# dosimeter.net
KiCad netlist of a schematic drawn in EAGLE
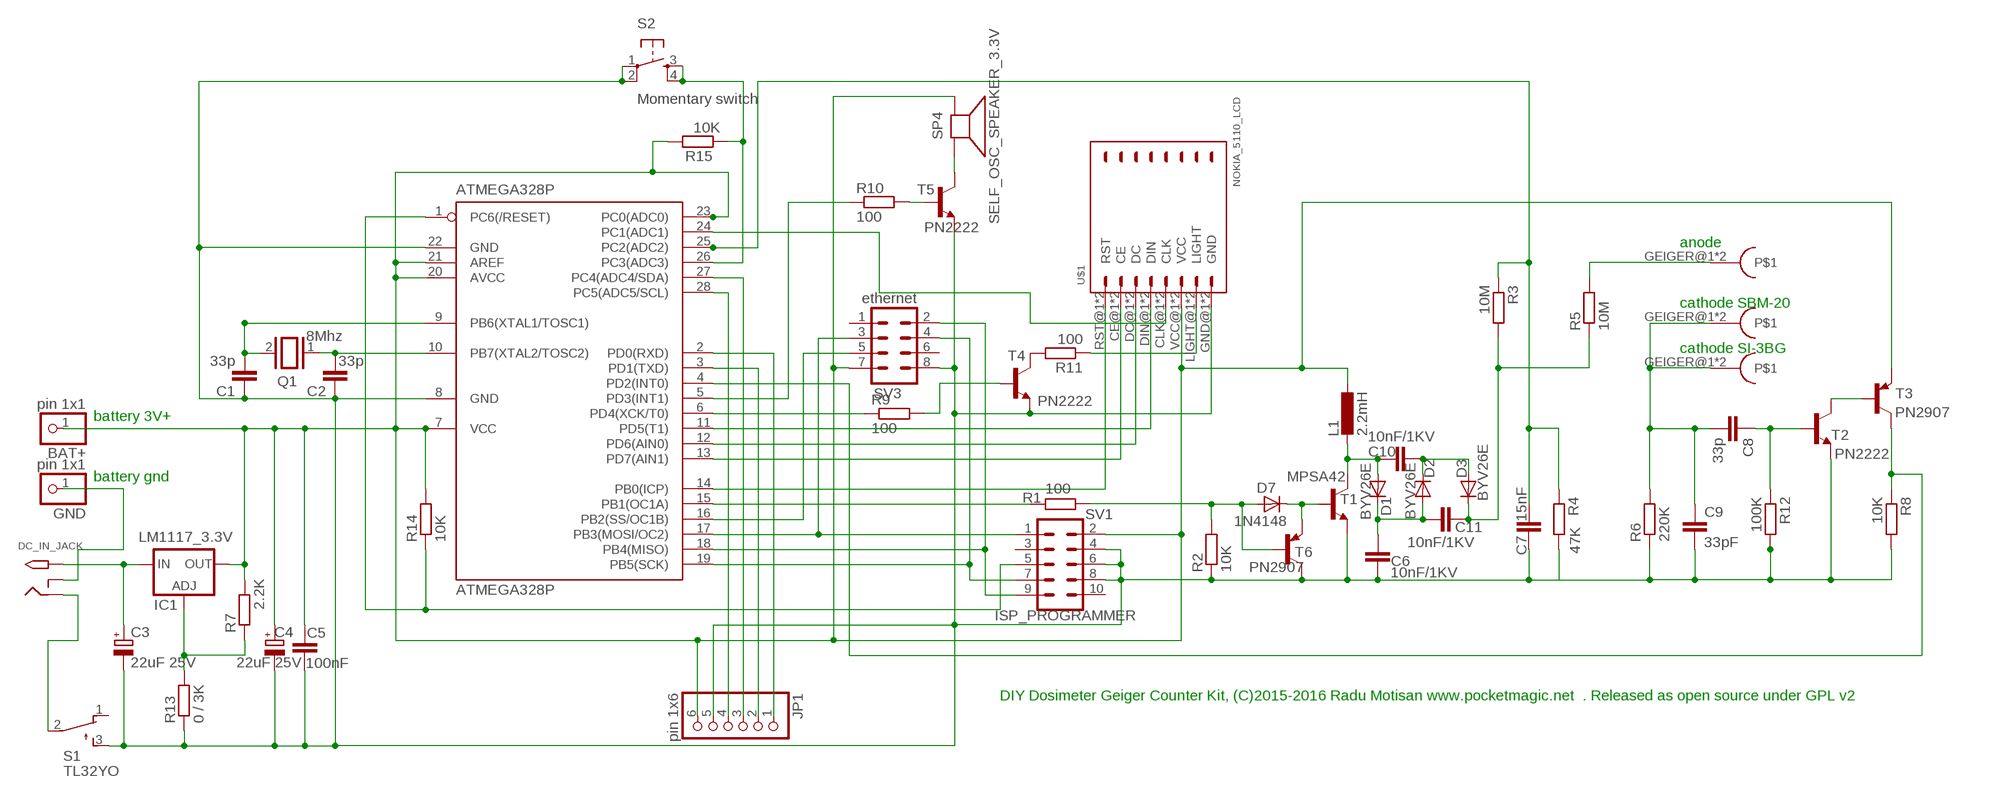
[diagram p0: schematic, sheet 1]

(export (version "E")
  (design (tool "Eeschema 10.0.6"))
  (components
    (comp (ref "ATMEGA328P")
      (value "ATMEGA328P")
      (footprint "eagle-import:DIL28-3")
      (libsource (lib "eagle-import") (part "MEGA8-P"))
    )
    (comp (ref "BAT+")
      (value "pin 1x1")
      (footprint "eagle-import:1X01")
      (libsource (lib "eagle-import") (part "PINHD-1X1"))
    )
    (comp (ref "C1")
      (value "33p")
      (footprint "eagle-import:C2.5-2")
      (libsource (lib "eagle-import") (part "C2.5/2"))
    )
    (comp (ref "C2")
      (value "33p")
      (footprint "eagle-import:C2.5-2")
      (libsource (lib "eagle-import") (part "C2.5/2"))
    )
    (comp (ref "C3")
      (value "22uF 25V")
      (footprint "eagle-import:E2-5")
      (libsource (lib "eagle-import") (part "CPOL-EUE2-5"))
    )
    (comp (ref "C4")
      (value "22uF 25V")
      (footprint "eagle-import:E2-5")
      (libsource (lib "eagle-import") (part "CPOL-EUE2-5"))
    )
    (comp (ref "C5")
      (value "100nF")
      (footprint "eagle-import:C2.5-2")
      (libsource (lib "eagle-import") (part "C2.5/2"))
    )
    (comp (ref "C6")
      (value "10nF/1KV")
      (footprint "eagle-import:C5B3")
      (libsource (lib "eagle-import") (part "C5/3"))
    )
    (comp (ref "C7")
      (value "15nF")
      (footprint "eagle-import:C2.5-2")
      (libsource (lib "eagle-import") (part "C2.5/2"))
    )
    (comp (ref "C8")
      (value "33p")
      (footprint "eagle-import:C2.5-2")
      (libsource (lib "eagle-import") (part "C2.5/2"))
    )
    (comp (ref "C9")
      (value "33pF")
      (footprint "eagle-import:C2.5-2")
      (libsource (lib "eagle-import") (part "C2.5/2"))
    )
    (comp (ref "C10")
      (value "10nF/1KV")
      (footprint "eagle-import:C5B3")
      (libsource (lib "eagle-import") (part "C5/3"))
    )
    (comp (ref "C11")
      (value "10nF/1KV")
      (footprint "eagle-import:C5B3")
      (libsource (lib "eagle-import") (part "C5/3"))
    )
    (comp (ref "CONNECTOR1")
      (value "Fuse connector 6mm")
      (footprint "eagle-import:GEIGER_CONNECTOR")
      (libsource (lib "eagle-import") (part "GEIGER_CONNECTOR"))
    )
    (comp (ref "CONNECTOR2")
      (value "Fuse connector 6mm")
      (footprint "eagle-import:GEIGER_CONNECTOR")
      (libsource (lib "eagle-import") (part "GEIGER_CONNECTOR"))
    )
    (comp (ref "CONNECTOR3")
      (value "Fuse connector 6mm")
      (footprint "eagle-import:GEIGER_CONNECTOR")
      (libsource (lib "eagle-import") (part "GEIGER_CONNECTOR"))
    )
    (comp (ref "D1")
      (value "BYV26E")
      (footprint "eagle-import:D-7.5")
      (libsource (lib "eagle-import") (part "1N40047.5"))
    )
    (comp (ref "D2")
      (value "BYV26E")
      (footprint "eagle-import:D-7.5")
      (libsource (lib "eagle-import") (part "1N40047.5"))
    )
    (comp (ref "D3")
      (value "BYV26E")
      (footprint "eagle-import:D-7.5")
      (libsource (lib "eagle-import") (part "1N40047.5"))
    )
    (comp (ref "D7")
      (value "1N4148")
      (footprint "eagle-import:DO35-7")
      (libsource (lib "eagle-import") (part "1N4148DO35-7"))
    )
    (comp (ref "DC_IN_JACK")
      (value "DC IN JACK")
      (footprint "eagle-import:PJ-102A")
      (libsource (lib "eagle-import") (part "2.1MMJACKTHM"))
    )
    (comp (ref "GND")
      (value "pin 1x1")
      (footprint "eagle-import:1X01")
      (libsource (lib "eagle-import") (part "PINHD-1X1"))
    )
    (comp (ref "IC1")
      (value "LM1117_3.3V")
      (footprint "eagle-import:TO220L1")
      (libsource (lib "eagle-import") (part "LD117A?V"))
    )
    (comp (ref "JP1")
      (value "pin 1x6")
      (footprint "eagle-import:1X06-CLEAN")
      (libsource (lib "eagle-import") (part "PINHD-1X6CLEAN"))
    )
    (comp (ref "L1")
      (value "2.2mH")
      (footprint "eagle-import:0207_10")
      (libsource (lib "eagle-import") (part "L-EU0207/10"))
    )
    (comp (ref "Q1")
      (value "8Mhz")
      (footprint "eagle-import:QS")
      (libsource (lib "eagle-import") (part "XTAL/S"))
    )
    (comp (ref "R1")
      (value "100")
      (footprint "eagle-import:0204_7")
      (libsource (lib "eagle-import") (part "R-EU_0204/7"))
    )
    (comp (ref "R2")
      (value "10K")
      (footprint "eagle-import:0204_7")
      (libsource (lib "eagle-import") (part "R-EU_0204/7"))
    )
    (comp (ref "R3")
      (value "10M")
      (footprint "eagle-import:0204_7")
      (libsource (lib "eagle-import") (part "R-EU_0204/7"))
    )
    (comp (ref "R4")
      (value "47K")
      (footprint "eagle-import:0204_7")
      (libsource (lib "eagle-import") (part "R-EU_0204/7"))
    )
    (comp (ref "R5")
      (value "10M")
      (footprint "eagle-import:0204_7")
      (libsource (lib "eagle-import") (part "R-EU_0204/7"))
    )
    (comp (ref "R6")
      (value "220K")
      (footprint "eagle-import:0204_7")
      (libsource (lib "eagle-import") (part "R-EU_0204/7"))
    )
    (comp (ref "R7")
      (value "2.2K")
      (footprint "eagle-import:0204_7")
      (libsource (lib "eagle-import") (part "R-EU_0204/7"))
    )
    (comp (ref "R8")
      (value "10K")
      (footprint "eagle-import:0204_7")
      (libsource (lib "eagle-import") (part "R-EU_0204/7"))
    )
    (comp (ref "R9")
      (value "100")
      (footprint "eagle-import:0204_7")
      (libsource (lib "eagle-import") (part "R-EU_0204/7"))
    )
    (comp (ref "R10")
      (value "100")
      (footprint "eagle-import:0204_7")
      (libsource (lib "eagle-import") (part "R-EU_0204/7"))
    )
    (comp (ref "R11")
      (value "100")
      (footprint "eagle-import:0204_7")
      (libsource (lib "eagle-import") (part "R-EU_0204/7"))
    )
    (comp (ref "R12")
      (value "100K")
      (footprint "eagle-import:0204_7")
      (libsource (lib "eagle-import") (part "R-EU_0204/7"))
    )
    (comp (ref "R13")
      (value "0 / 3K")
      (footprint "eagle-import:0204_7")
      (libsource (lib "eagle-import") (part "R-EU_0204/7"))
    )
    (comp (ref "R14")
      (value "10K")
      (footprint "eagle-import:0204_7")
      (libsource (lib "eagle-import") (part "R-EU_0204/7"))
    )
    (comp (ref "R15")
      (value "10K")
      (footprint "eagle-import:0204_7")
      (libsource (lib "eagle-import") (part "R-EU_0204/7"))
    )
    (comp (ref "S1")
      (value "TL32YO")
      (footprint "eagle-import:TL3XYO")
      (libsource (lib "eagle-import") (part "TL32YO"))
    )
    (comp (ref "S2")
      (value "Momentary switch")
      (footprint "eagle-import:TACTILE-PTH")
      (libsource (lib "eagle-import") (part "TAC_SWITCHPTH"))
    )
    (comp (ref "SP4")
      (value "SELF_OSC_SPEAKER_3.3V")
      (footprint "eagle-import:AL60P")
      (libsource (lib "eagle-import") (part "SPEAKER/AL60P"))
    )
    (comp (ref "SV1")
      (value "ISP_PROGRAMMER")
      (footprint "eagle-import:MA05-2")
      (libsource (lib "eagle-import") (part "MA05-2"))
    )
    (comp (ref "SV3")
      (value "ethernet")
      (footprint "eagle-import:MA04-2")
      (libsource (lib "eagle-import") (part "MA04-2"))
    )
    (comp (ref "T1")
      (value "MPSA42")
      (footprint "eagle-import:TO92-EBC-OVAL")
      (libsource (lib "eagle-import") (part "2N2222"))
    )
    (comp (ref "T2")
      (value "PN2222")
      (footprint "eagle-import:TO92-EBC-OVAL")
      (libsource (lib "eagle-import") (part "2N2222"))
    )
    (comp (ref "T3")
      (value "PN2907")
      (footprint "eagle-import:TO92-EBC-OVAL")
      (libsource (lib "eagle-import") (part "2N2907"))
    )
    (comp (ref "T4")
      (value "PN2222")
      (footprint "eagle-import:TO92-EBC")
      (libsource (lib "eagle-import") (part "-NPN-TO92-EBC2N2222"))
    )
    (comp (ref "T5")
      (value "PN2222")
      (footprint "eagle-import:TO92-EBC")
      (libsource (lib "eagle-import") (part "-NPN-TO92-EBC2N2222"))
    )
    (comp (ref "T6")
      (value "PN2907")
      (footprint "eagle-import:TO92-EBC-OVAL")
      (libsource (lib "eagle-import") (part "2N2907"))
    )
    (comp (ref "U$1")
      (value "NOKIA_5110_LCD")
      (footprint "eagle-import:NOKIA5110")
      (libsource (lib "eagle-import") (part "NOKIA5110"))
    )
  )
  (nets
    (net (code "1") (name "Net-(ATMEGA328P-AREF)") (class "Default")
      (node (ref "ATMEGA328P") (pin "20") (pinfunction "AVCC_20") (pintype "power_in"))
      (node (ref "ATMEGA328P") (pin "21") (pinfunction "AREF_21") (pintype "passive"))
      (node (ref "ATMEGA328P") (pin "23") (pinfunction "PC0(ADC0)_23") (pintype "bidirectional"))
      (node (ref "ATMEGA328P") (pin "7") (pinfunction "VCC_7") (pintype "power_in"))
      (node (ref "BAT+") (pin "1") (pinfunction "1_1") (pintype "passive"))
      (node (ref "C4") (pin "+") (pinfunction "+_+") (pintype "passive"))
      (node (ref "C5") (pin "2") (pinfunction "2_2") (pintype "passive"))
      (node (ref "IC1") (pin "2") (pinfunction "OUT_2") (pintype "passive"))
      (node (ref "JP1") (pin "6") (pinfunction "6_6") (pintype "passive"))
      (node (ref "L1") (pin "1") (pinfunction "1_1") (pintype "passive"))
      (node (ref "R14") (pin "2") (pinfunction "2_2") (pintype "passive"))
      (node (ref "R15") (pin "2") (pinfunction "2_2") (pintype "passive"))
      (node (ref "R7") (pin "2") (pinfunction "2_2") (pintype "passive"))
      (node (ref "SP4") (pin "1") (pinfunction "+_1") (pintype "passive"))
      (node (ref "SV1") (pin "2") (pinfunction "2_2") (pintype "passive"))
      (node (ref "SV3") (pin "7") (pinfunction "7_7") (pintype "passive"))
      (node (ref "T3") (pin "E") (pinfunction "E_E") (pintype "passive"))
      (node (ref "U$1") (pin "VCC@1") (pinfunction "VCC_VCC@1") (pintype "bidirectional"))
      (node (ref "U$1") (pin "VCC@2") (pinfunction "VCC_VCC@2") (pintype "bidirectional"))
    )
    (net (code "2") (name "Net-(ATMEGA328P-PB0(ICP))") (class "Default")
      (node (ref "ATMEGA328P") (pin "14") (pinfunction "PB0(ICP)_14") (pintype "bidirectional"))
      (node (ref "U$1") (pin "RST@1") (pinfunction "RST_RST@1") (pintype "bidirectional"))
      (node (ref "U$1") (pin "RST@2") (pinfunction "RST_RST@2") (pintype "bidirectional"))
    )
    (net (code "3") (name "Net-(ATMEGA328P-PB1(OC1A))") (class "Default")
      (node (ref "ATMEGA328P") (pin "15") (pinfunction "PB1(OC1A)_15") (pintype "bidirectional"))
      (node (ref "R1") (pin "1") (pinfunction "1_1") (pintype "passive"))
    )
    (net (code "4") (name "Net-(ATMEGA328P-PB2(SS{slash}OC1B))") (class "Default")
      (node (ref "ATMEGA328P") (pin "16") (pinfunction "PB2(SS/OC1B)_16") (pintype "bidirectional"))
      (node (ref "SV3") (pin "5") (pinfunction "5_5") (pintype "passive"))
    )
    (net (code "5") (name "Net-(ATMEGA328P-PB3(MOSI{slash}OC2))") (class "Default")
      (node (ref "ATMEGA328P") (pin "17") (pinfunction "PB3(MOSI/OC2)_17") (pintype "bidirectional"))
      (node (ref "SV1") (pin "1") (pinfunction "1_1") (pintype "passive"))
      (node (ref "SV3") (pin "3") (pinfunction "3_3") (pintype "passive"))
    )
    (net (code "6") (name "Net-(ATMEGA328P-PB4(MISO))") (class "Default")
      (node (ref "ATMEGA328P") (pin "18") (pinfunction "PB4(MISO)_18") (pintype "bidirectional"))
      (node (ref "SV1") (pin "9") (pinfunction "9_9") (pintype "passive"))
      (node (ref "SV3") (pin "2") (pinfunction "2_2") (pintype "passive"))
    )
    (net (code "7") (name "Net-(ATMEGA328P-PB5(SCK))") (class "Default")
      (node (ref "ATMEGA328P") (pin "19") (pinfunction "PB5(SCK)_19") (pintype "bidirectional"))
      (node (ref "SV1") (pin "7") (pinfunction "7_7") (pintype "passive"))
      (node (ref "SV3") (pin "4") (pinfunction "4_4") (pintype "passive"))
    )
    (net (code "8") (name "Net-(ATMEGA328P-PB6(XTAL1{slash}TOSC1))") (class "Default")
      (node (ref "ATMEGA328P") (pin "9") (pinfunction "PB6(XTAL1/TOSC1)_9") (pintype "bidirectional"))
      (node (ref "C1") (pin "2") (pinfunction "2_2") (pintype "passive"))
      (node (ref "Q1") (pin "2") (pinfunction "2_2") (pintype "passive"))
    )
    (net (code "9") (name "Net-(ATMEGA328P-PB7(XTAL2{slash}TOSC2))") (class "Default")
      (node (ref "ATMEGA328P") (pin "10") (pinfunction "PB7(XTAL2/TOSC2)_10") (pintype "bidirectional"))
      (node (ref "C2") (pin "2") (pinfunction "2_2") (pintype "passive"))
      (node (ref "Q1") (pin "1") (pinfunction "1_1") (pintype "passive"))
    )
    (net (code "10") (name "Net-(ATMEGA328P-PC1(ADC1))") (class "Default")
      (node (ref "ATMEGA328P") (pin "24") (pinfunction "PC1(ADC1)_24") (pintype "bidirectional"))
      (node (ref "U$1") (pin "CLK@1") (pinfunction "CLK_CLK@1") (pintype "bidirectional"))
      (node (ref "U$1") (pin "CLK@2") (pinfunction "CLK_CLK@2") (pintype "bidirectional"))
    )
    (net (code "11") (name "Net-(ATMEGA328P-PC2(ADC2))") (class "Default")
      (node (ref "ATMEGA328P") (pin "25") (pinfunction "PC2(ADC2)_25") (pintype "bidirectional"))
      (node (ref "C7") (pin "2") (pinfunction "2_2") (pintype "passive"))
      (node (ref "R3") (pin "1") (pinfunction "1_1") (pintype "passive"))
      (node (ref "R4") (pin "1") (pinfunction "1_1") (pintype "passive"))
    )
    (net (code "12") (name "Net-(ATMEGA328P-PC3(ADC3))") (class "Default")
      (node (ref "ATMEGA328P") (pin "26") (pinfunction "PC3(ADC3)_26") (pintype "bidirectional"))
      (node (ref "R15") (pin "1") (pinfunction "1_1") (pintype "passive"))
      (node (ref "S2") (pin "3") (pinfunction "3_3") (pintype "passive"))
      (node (ref "S2") (pin "4") (pinfunction "4_4") (pintype "passive"))
    )
    (net (code "13") (name "Net-(ATMEGA328P-PC4(ADC4{slash}SDA))") (class "Default")
      (node (ref "ATMEGA328P") (pin "27") (pinfunction "PC4(ADC4/SDA)_27") (pintype "bidirectional"))
      (node (ref "JP1") (pin "3") (pinfunction "3_3") (pintype "passive"))
    )
    (net (code "14") (name "Net-(ATMEGA328P-PC5(ADC5{slash}SCL))") (class "Default")
      (node (ref "ATMEGA328P") (pin "28") (pinfunction "PC5(ADC5/SCL)_28") (pintype "bidirectional"))
      (node (ref "JP1") (pin "4") (pinfunction "4_4") (pintype "passive"))
    )
    (net (code "15") (name "Net-(ATMEGA328P-PC6({slash}RESET))") (class "Default")
      (node (ref "ATMEGA328P") (pin "1") (pinfunction "PC6(/RESET)_1") (pintype "bidirectional"))
      (node (ref "R14") (pin "1") (pinfunction "1_1") (pintype "passive"))
      (node (ref "SV1") (pin "5") (pinfunction "5_5") (pintype "passive"))
    )
    (net (code "16") (name "Net-(ATMEGA328P-PD0(RXD))") (class "Default")
      (node (ref "ATMEGA328P") (pin "2") (pinfunction "PD0(RXD)_2") (pintype "bidirectional"))
      (node (ref "JP1") (pin "1") (pinfunction "1_1") (pintype "passive"))
    )
    (net (code "17") (name "Net-(ATMEGA328P-PD1(TXD))") (class "Default")
      (node (ref "ATMEGA328P") (pin "3") (pinfunction "PD1(TXD)_3") (pintype "bidirectional"))
      (node (ref "JP1") (pin "2") (pinfunction "2_2") (pintype "passive"))
    )
    (net (code "18") (name "Net-(ATMEGA328P-PD2(INT0))") (class "Default")
      (node (ref "ATMEGA328P") (pin "4") (pinfunction "PD2(INT0)_4") (pintype "bidirectional"))
      (node (ref "R8") (pin "1") (pinfunction "1_1") (pintype "passive"))
      (node (ref "T3") (pin "C") (pinfunction "C_C") (pintype "passive"))
    )
    (net (code "19") (name "Net-(ATMEGA328P-PD3(INT1))") (class "Default")
      (node (ref "ATMEGA328P") (pin "5") (pinfunction "PD3(INT1)_5") (pintype "bidirectional"))
      (node (ref "R10") (pin "1") (pinfunction "1_1") (pintype "passive"))
    )
    (net (code "20") (name "Net-(ATMEGA328P-PD4(XCK{slash}T0))") (class "Default")
      (node (ref "ATMEGA328P") (pin "6") (pinfunction "PD4(XCK/T0)_6") (pintype "bidirectional"))
      (node (ref "R9") (pin "1") (pinfunction "1_1") (pintype "passive"))
    )
    (net (code "21") (name "Net-(ATMEGA328P-PD5(T1))") (class "Default")
      (node (ref "ATMEGA328P") (pin "11") (pinfunction "PD5(T1)_11") (pintype "bidirectional"))
      (node (ref "U$1") (pin "DIN@1") (pinfunction "DIN_DIN@1") (pintype "bidirectional"))
      (node (ref "U$1") (pin "DIN@2") (pinfunction "DIN_DIN@2") (pintype "bidirectional"))
    )
    (net (code "22") (name "Net-(ATMEGA328P-PD6(AIN0))") (class "Default")
      (node (ref "ATMEGA328P") (pin "12") (pinfunction "PD6(AIN0)_12") (pintype "bidirectional"))
      (node (ref "U$1") (pin "DC@1") (pinfunction "DC_DC@1") (pintype "bidirectional"))
      (node (ref "U$1") (pin "DC@2") (pinfunction "DC_DC@2") (pintype "bidirectional"))
    )
    (net (code "23") (name "Net-(ATMEGA328P-PD7(AIN1))") (class "Default")
      (node (ref "ATMEGA328P") (pin "13") (pinfunction "PD7(AIN1)_13") (pintype "bidirectional"))
      (node (ref "U$1") (pin "CE@1") (pinfunction "CE_CE@1") (pintype "bidirectional"))
      (node (ref "U$1") (pin "CE@2") (pinfunction "CE_CE@2") (pintype "bidirectional"))
    )
    (net (code "24") (name "Net-(C8-Pad1)") (class "Default")
      (node (ref "C8") (pin "1") (pinfunction "1_1") (pintype "passive"))
      (node (ref "R12") (pin "1") (pinfunction "1_1") (pintype "passive"))
      (node (ref "T2") (pin "B") (pinfunction "B_B") (pintype "passive"))
    )
    (net (code "25") (name "Net-(C8-Pad2)") (class "Default")
      (node (ref "C8") (pin "2") (pinfunction "2_2") (pintype "passive"))
      (node (ref "C9") (pin "1") (pinfunction "1_1") (pintype "passive"))
      (node (ref "CONNECTOR1") (pin "GEIGER@1") (pinfunction "P$1_GEIGER@1") (pintype "bidirectional"))
      (node (ref "CONNECTOR1") (pin "GEIGER@2") (pinfunction "P$1_GEIGER@2") (pintype "bidirectional"))
      (node (ref "CONNECTOR2") (pin "GEIGER@1") (pinfunction "P$1_GEIGER@1") (pintype "bidirectional"))
      (node (ref "CONNECTOR2") (pin "GEIGER@2") (pinfunction "P$1_GEIGER@2") (pintype "bidirectional"))
      (node (ref "R6") (pin "2") (pinfunction "2_2") (pintype "passive"))
    )
    (net (code "26") (name "Net-(C10-Pad1)") (class "Default")
      (node (ref "C10") (pin "1") (pinfunction "1_1") (pintype "passive"))
      (node (ref "D2") (pin "C") (pinfunction "C_C") (pintype "passive"))
      (node (ref "D3") (pin "A") (pinfunction "A_A") (pintype "passive"))
    )
    (net (code "27") (name "Net-(C10-Pad2)") (class "Default")
      (node (ref "C10") (pin "2") (pinfunction "2_2") (pintype "passive"))
      (node (ref "D1") (pin "A") (pinfunction "A_A") (pintype "passive"))
      (node (ref "L1") (pin "2") (pinfunction "2_2") (pintype "passive"))
      (node (ref "T1") (pin "C") (pinfunction "C_C") (pintype "passive"))
    )
    (net (code "28") (name "Net-(C11-Pad1)") (class "Default")
      (node (ref "C11") (pin "1") (pinfunction "1_1") (pintype "passive"))
      (node (ref "D3") (pin "C") (pinfunction "C_C") (pintype "passive"))
      (node (ref "R3") (pin "2") (pinfunction "2_2") (pintype "passive"))
      (node (ref "R5") (pin "1") (pinfunction "1_1") (pintype "passive"))
    )
    (net (code "29") (name "Net-(C11-Pad2)") (class "Default")
      (node (ref "C11") (pin "2") (pinfunction "2_2") (pintype "passive"))
      (node (ref "C6") (pin "1") (pinfunction "1_1") (pintype "passive"))
      (node (ref "D1") (pin "C") (pinfunction "C_C") (pintype "passive"))
      (node (ref "D2") (pin "A") (pinfunction "A_A") (pintype "passive"))
    )
    (net (code "30") (name "Net-(CONNECTOR3-P$1-PadGEIGER@1)") (class "Default")
      (node (ref "CONNECTOR3") (pin "GEIGER@1") (pinfunction "P$1_GEIGER@1") (pintype "bidirectional"))
      (node (ref "CONNECTOR3") (pin "GEIGER@2") (pinfunction "P$1_GEIGER@2") (pintype "bidirectional"))
      (node (ref "R5") (pin "2") (pinfunction "2_2") (pintype "passive"))
    )
    (net (code "31") (name "Net-(D7-PadA)") (class "Default")
      (node (ref "D7") (pin "A") (pinfunction "A_A") (pintype "passive"))
      (node (ref "R1") (pin "2") (pinfunction "2_2") (pintype "passive"))
      (node (ref "R2") (pin "2") (pinfunction "2_2") (pintype "passive"))
      (node (ref "T6") (pin "B") (pinfunction "B_B") (pintype "passive"))
    )
    (net (code "32") (name "Net-(D7-PadC)") (class "Default")
      (node (ref "D7") (pin "C") (pinfunction "C_C") (pintype "passive"))
      (node (ref "T1") (pin "B") (pinfunction "B_B") (pintype "passive"))
      (node (ref "T6") (pin "E") (pinfunction "E_E") (pintype "passive"))
    )
    (net (code "33") (name "Net-(DC_IN_JACK-PadRING_SW)") (class "Default")
      (node (ref "DC_IN_JACK") (pin "RING_SW") (pinfunction "RING_SW_RING_SW") (pintype "bidirectional"))
      (node (ref "GND") (pin "1") (pinfunction "1_1") (pintype "passive"))
    )
    (net (code "34") (name "Net-(IC1-ADJ)") (class "Default")
      (node (ref "IC1") (pin "1") (pinfunction "ADJ_1") (pintype "input"))
      (node (ref "R13") (pin "2") (pinfunction "2_2") (pintype "passive"))
      (node (ref "R7") (pin "1") (pinfunction "1_1") (pintype "passive"))
    )
    (net (code "35") (name "Net-(IC1-IN)") (class "Default")
      (node (ref "C3") (pin "+") (pinfunction "+_+") (pintype "passive"))
      (node (ref "DC_IN_JACK") (pin "TIP") (pinfunction "TIP_TIP") (pintype "bidirectional"))
      (node (ref "IC1") (pin "3") (pinfunction "IN_3") (pintype "input"))
    )
    (net (code "36") (name "Net-(R9-Pad2)") (class "Default")
      (node (ref "R9") (pin "2") (pinfunction "2_2") (pintype "passive"))
      (node (ref "T4") (pin "B") (pinfunction "B_B") (pintype "passive"))
    )
    (net (code "37") (name "Net-(R10-Pad2)") (class "Default")
      (node (ref "R10") (pin "2") (pinfunction "2_2") (pintype "passive"))
      (node (ref "T5") (pin "B") (pinfunction "B_B") (pintype "passive"))
    )
    (net (code "38") (name "Net-(R11-Pad1)") (class "Default")
      (node (ref "R11") (pin "1") (pinfunction "1_1") (pintype "passive"))
      (node (ref "U$1") (pin "LIGHT@1") (pinfunction "LIGHT_LIGHT@1") (pintype "bidirectional"))
      (node (ref "U$1") (pin "LIGHT@2") (pinfunction "LIGHT_LIGHT@2") (pintype "bidirectional"))
    )
    (net (code "39") (name "Net-(R11-Pad2)") (class "Default")
      (node (ref "R11") (pin "2") (pinfunction "2_2") (pintype "passive"))
      (node (ref "T4") (pin "C") (pinfunction "C_C") (pintype "passive"))
    )
    (net (code "40") (name "Net-(S1-P)") (class "Default")
      (node (ref "DC_IN_JACK") (pin "RING") (pinfunction "RING_RING") (pintype "bidirectional"))
      (node (ref "S1") (pin "2") (pinfunction "P_2") (pintype "passive"))
    )
    (net (code "41") (name "Net-(S1-S)") (class "Default")
      (node (ref "ATMEGA328P") (pin "22") (pinfunction "GND_22") (pintype "power_in"))
      (node (ref "ATMEGA328P") (pin "8") (pinfunction "GND_8") (pintype "power_in"))
      (node (ref "C1") (pin "1") (pinfunction "1_1") (pintype "passive"))
      (node (ref "C2") (pin "1") (pinfunction "1_1") (pintype "passive"))
      (node (ref "C3") (pin "-") (pinfunction "-_-") (pintype "passive"))
      (node (ref "C4") (pin "-") (pinfunction "-_-") (pintype "passive"))
      (node (ref "C5") (pin "1") (pinfunction "1_1") (pintype "passive"))
      (node (ref "C6") (pin "2") (pinfunction "2_2") (pintype "passive"))
      (node (ref "C7") (pin "1") (pinfunction "1_1") (pintype "passive"))
      (node (ref "C9") (pin "2") (pinfunction "2_2") (pintype "passive"))
      (node (ref "JP1") (pin "5") (pinfunction "5_5") (pintype "passive"))
      (node (ref "R12") (pin "2") (pinfunction "2_2") (pintype "passive"))
      (node (ref "R13") (pin "1") (pinfunction "1_1") (pintype "passive"))
      (node (ref "R2") (pin "1") (pinfunction "1_1") (pintype "passive"))
      (node (ref "R4") (pin "2") (pinfunction "2_2") (pintype "passive"))
      (node (ref "R6") (pin "1") (pinfunction "1_1") (pintype "passive"))
      (node (ref "R8") (pin "2") (pinfunction "2_2") (pintype "passive"))
      (node (ref "S1") (pin "3") (pinfunction "S_3") (pintype "passive"))
      (node (ref "S2") (pin "1") (pinfunction "1_1") (pintype "passive"))
      (node (ref "S2") (pin "2") (pinfunction "2_2") (pintype "passive"))
      (node (ref "SV1") (pin "4") (pinfunction "4_4") (pintype "passive"))
      (node (ref "SV1") (pin "6") (pinfunction "6_6") (pintype "passive"))
      (node (ref "SV1") (pin "8") (pinfunction "8_8") (pintype "passive"))
      (node (ref "SV3") (pin "8") (pinfunction "8_8") (pintype "passive"))
      (node (ref "T1") (pin "E") (pinfunction "E_E") (pintype "passive"))
      (node (ref "T2") (pin "E") (pinfunction "E_E") (pintype "passive"))
      (node (ref "T4") (pin "E") (pinfunction "E_E") (pintype "passive"))
      (node (ref "T5") (pin "E") (pinfunction "E_E") (pintype "passive"))
      (node (ref "T6") (pin "C") (pinfunction "C_C") (pintype "passive"))
      (node (ref "U$1") (pin "GND@1") (pinfunction "GND_GND@1") (pintype "bidirectional"))
      (node (ref "U$1") (pin "GND@2") (pinfunction "GND_GND@2") (pintype "bidirectional"))
    )
    (net (code "42") (name "Net-(SP4--)") (class "Default")
      (node (ref "SP4") (pin "2") (pinfunction "-_2") (pintype "passive"))
      (node (ref "T5") (pin "C") (pinfunction "C_C") (pintype "passive"))
    )
    (net (code "43") (name "Net-(T2-PadC)") (class "Default")
      (node (ref "T2") (pin "C") (pinfunction "C_C") (pintype "passive"))
      (node (ref "T3") (pin "B") (pinfunction "B_B") (pintype "passive"))
    )
    (net (code "44") (name "unconnected-(S1-O-Pad1)") (class "Default")
      (node (ref "S1") (pin "1") (pinfunction "O_1") (pintype "passive"))
    )
    (net (code "45") (name "unconnected-(SV1-Pad3)") (class "Default")
      (node (ref "SV1") (pin "3") (pinfunction "3_3") (pintype "passive"))
    )
    (net (code "46") (name "unconnected-(SV1-Pad10)") (class "Default")
      (node (ref "SV1") (pin "10") (pinfunction "10_10") (pintype "passive"))
    )
    (net (code "47") (name "unconnected-(SV3-Pad1)") (class "Default")
      (node (ref "SV3") (pin "1") (pinfunction "1_1") (pintype "passive"))
    )
    (net (code "48") (name "unconnected-(SV3-Pad6)") (class "Default")
      (node (ref "SV3") (pin "6") (pinfunction "6_6") (pintype "passive"))
    )
  )
)
